# IRK.net
KiCad netlist of a schematic drawn in EAGLE
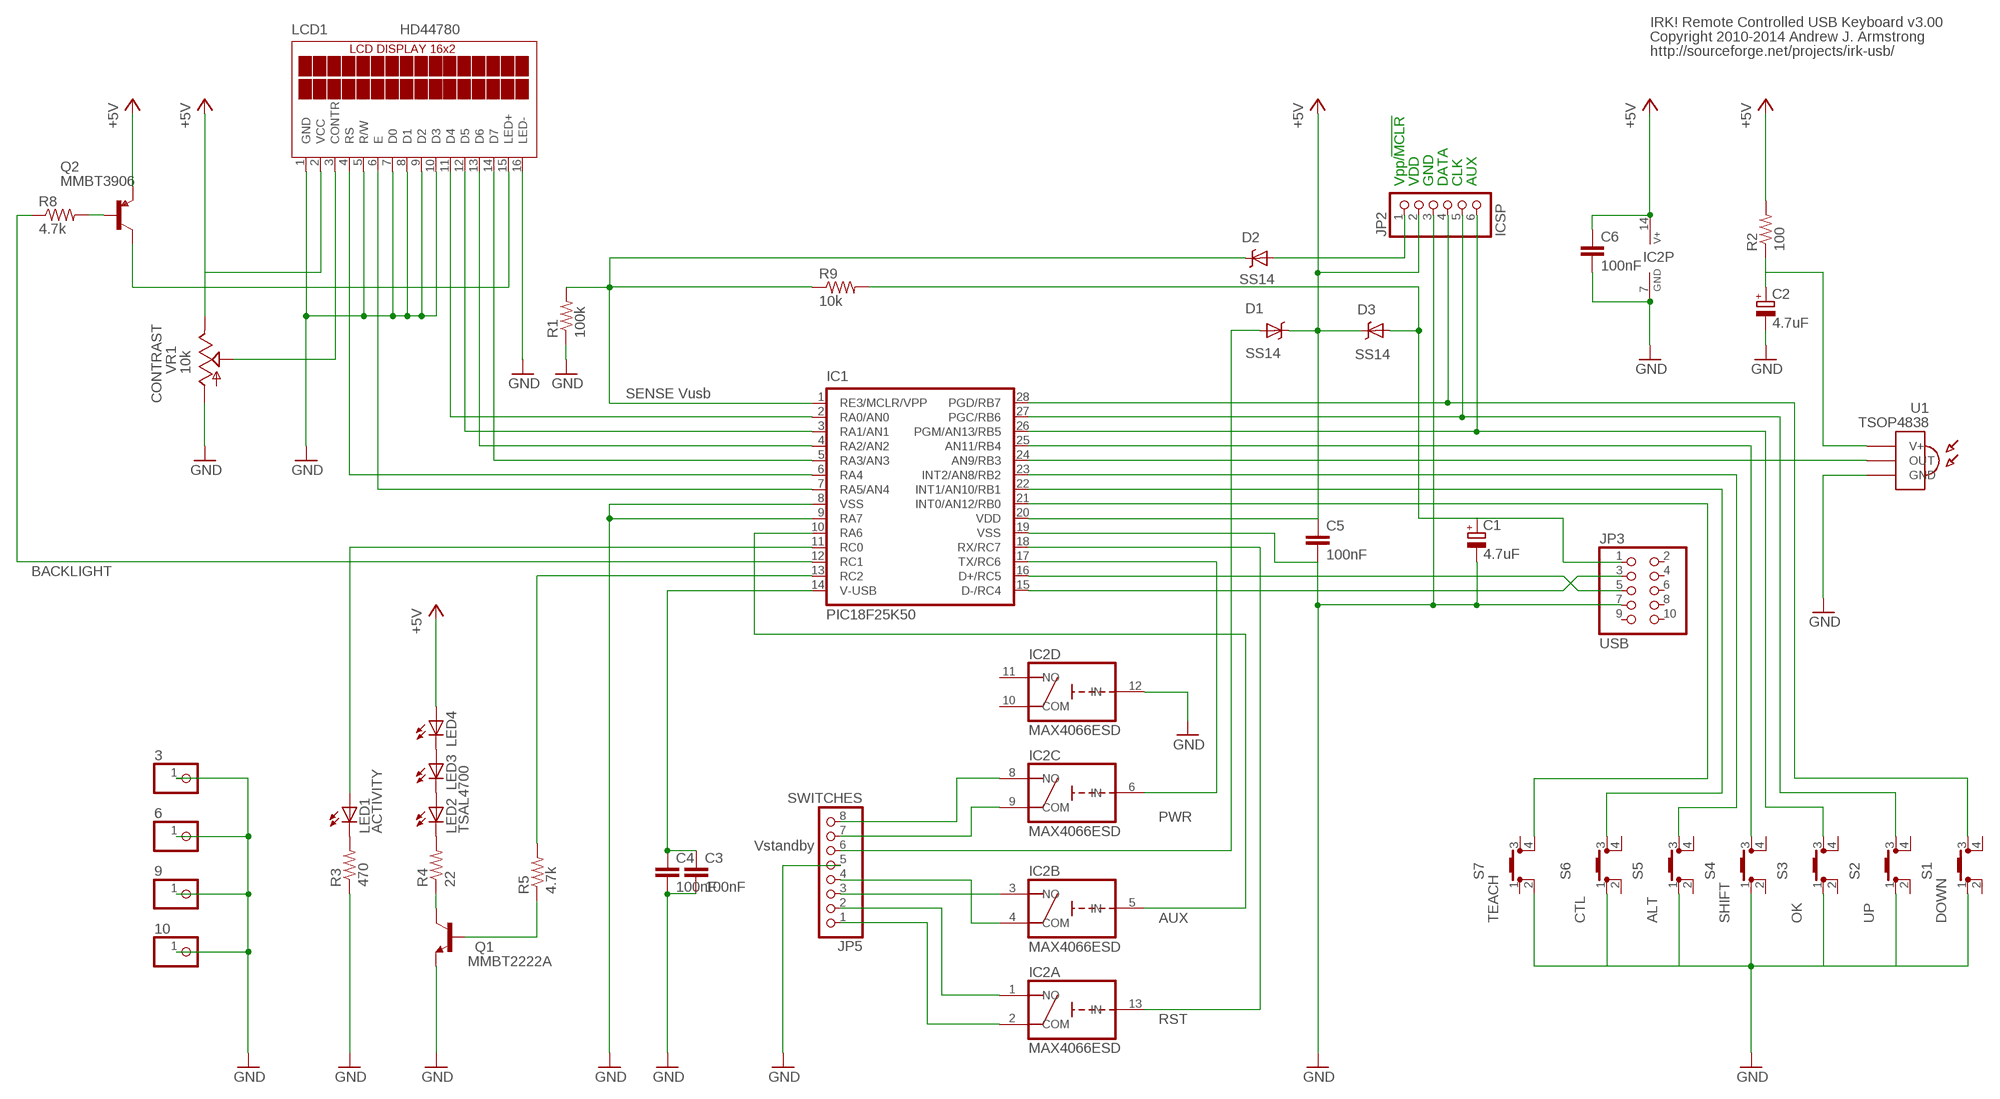
[diagram p0: schematic, sheet 1]

(export (version "E")
  (design (tool "Eeschema 10.0.6"))
  (components
    (comp (ref "3")
      (value "PINHD-1X1")
      (footprint "eagle-import:1X01")
      (libsource (lib "eagle-import") (part "PINHD-1X1"))
    )
    (comp (ref "6")
      (value "PINHD-1X1")
      (footprint "eagle-import:1X01")
      (libsource (lib "eagle-import") (part "PINHD-1X1"))
    )
    (comp (ref "9")
      (value "PINHD-1X1")
      (footprint "eagle-import:1X01")
      (libsource (lib "eagle-import") (part "PINHD-1X1"))
    )
    (comp (ref "10")
      (value "PINHD-1X1")
      (footprint "eagle-import:1X01")
      (libsource (lib "eagle-import") (part "PINHD-1X1"))
    )
    (comp (ref "C1")
      (value "4.7uF")
      (footprint "eagle-import:SMC_A")
      (libsource (lib "eagle-import") (part "CPOL-EUSMCA"))
    )
    (comp (ref "C2")
      (value "4.7uF")
      (footprint "eagle-import:SMC_A")
      (libsource (lib "eagle-import") (part "CPOL-EUSMCA"))
    )
    (comp (ref "C3")
      (value "100nF")
      (footprint "eagle-import:C0805")
      (libsource (lib "eagle-import") (part "C-EUC0805"))
    )
    (comp (ref "C4")
      (value "100nF")
      (footprint "eagle-import:C0805")
      (libsource (lib "eagle-import") (part "C-EUC0805"))
    )
    (comp (ref "C5")
      (value "100nF")
      (footprint "eagle-import:C0805")
      (libsource (lib "eagle-import") (part "C-EUC0805"))
    )
    (comp (ref "C6")
      (value "100nF")
      (footprint "eagle-import:C0805")
      (libsource (lib "eagle-import") (part "C-EUC0805"))
    )
    (comp (ref "D1")
      (value "SS14")
      (footprint "eagle-import:SMA-DIODE")
      (libsource (lib "eagle-import") (part "SS14"))
    )
    (comp (ref "D2")
      (value "SS14")
      (footprint "eagle-import:SMA-DIODE")
      (libsource (lib "eagle-import") (part "SS14"))
    )
    (comp (ref "D3")
      (value "SS14")
      (footprint "eagle-import:SMA-DIODE")
      (libsource (lib "eagle-import") (part "SS14"))
    )
    (comp (ref "IC1")
      (value "PIC18F25K50")
      (footprint "eagle-import:SO28W")
      (libsource (lib "eagle-import") (part "PIC18F25K50SO28W"))
    )
    (comp (ref "IC2")
      (value "MAX4066ESD")
      (footprint "eagle-import:SO14")
      (libsource (lib "eagle-import") (part "MAX4066ESD"))
    )
    (comp (ref "JP2")
      (value "ICSP")
      (footprint "eagle-import:1X06")
      (libsource (lib "eagle-import") (part "PINHD-1X6"))
    )
    (comp (ref "JP3")
      (value "USB")
      (footprint "eagle-import:2X05")
      (libsource (lib "eagle-import") (part "PINHD-2X5"))
    )
    (comp (ref "JP5")
      (value "SWITCHES")
      (footprint "eagle-import:1X08")
      (libsource (lib "eagle-import") (part "PINHD-1X8"))
    )
    (comp (ref "LCD1")
      (value "HD44780")
      (footprint "eagle-import:LCD_16X2")
      (libsource (lib "eagle-import") (part "HD44780"))
    )
    (comp (ref "LED1")
      (value "ACTIVITY")
      (footprint "eagle-import:LED5MM")
      (libsource (lib "eagle-import") (part "LED5MM"))
    )
    (comp (ref "LED2")
      (value "TSAL4700")
      (footprint "eagle-import:LED5MM")
      (libsource (lib "eagle-import") (part "LED5MM"))
    )
    (comp (ref "LED3")
      (value "LED5MM")
      (footprint "eagle-import:LED5MM")
      (libsource (lib "eagle-import") (part "LED5MM"))
    )
    (comp (ref "LED4")
      (value "LED5MM")
      (footprint "eagle-import:LED5MM")
      (libsource (lib "eagle-import") (part "LED5MM"))
    )
    (comp (ref "Q1")
      (value "MMBT2222A")
      (footprint "eagle-import:SOT23")
      (libsource (lib "eagle-import") (part "MMBT2222A"))
    )
    (comp (ref "Q2")
      (value "MMBT3906")
      (footprint "eagle-import:SOT23")
      (libsource (lib "eagle-import") (part "MMBT3906SOT23"))
    )
    (comp (ref "R1")
      (value "100k")
      (footprint "eagle-import:M1206")
      (libsource (lib "eagle-import") (part "R-US_M1206"))
    )
    (comp (ref "R2")
      (value "100")
      (footprint "eagle-import:M1206")
      (libsource (lib "eagle-import") (part "R-US_M1206"))
    )
    (comp (ref "R3")
      (value "470")
      (footprint "eagle-import:M1206")
      (libsource (lib "eagle-import") (part "R-US_M1206"))
    )
    (comp (ref "R4")
      (value "22")
      (footprint "eagle-import:M1206")
      (libsource (lib "eagle-import") (part "R-US_M1206"))
    )
    (comp (ref "R5")
      (value "4.7k")
      (footprint "eagle-import:M1206")
      (libsource (lib "eagle-import") (part "R-US_M1206"))
    )
    (comp (ref "R8")
      (value "4.7k")
      (footprint "eagle-import:M1206")
      (libsource (lib "eagle-import") (part "R-US_M1206"))
    )
    (comp (ref "R9")
      (value "10k")
      (footprint "eagle-import:M1206")
      (libsource (lib "eagle-import") (part "R-US_M1206"))
    )
    (comp (ref "S1")
      (value "DOWN")
      (footprint "eagle-import:PTH525-SM10")
      (libsource (lib "eagle-import") (part "C&K-PTS525-SM10"))
    )
    (comp (ref "S2")
      (value "UP")
      (footprint "eagle-import:PTH525-SM10")
      (libsource (lib "eagle-import") (part "C&K-PTS525-SM10"))
    )
    (comp (ref "S3")
      (value "OK")
      (footprint "eagle-import:PTH525-SM10")
      (libsource (lib "eagle-import") (part "C&K-PTS525-SM10"))
    )
    (comp (ref "S4")
      (value "SHIFT")
      (footprint "eagle-import:PTH525-SM10")
      (libsource (lib "eagle-import") (part "C&K-PTS525-SM10"))
    )
    (comp (ref "S5")
      (value "ALT")
      (footprint "eagle-import:PTH525-SM10")
      (libsource (lib "eagle-import") (part "C&K-PTS525-SM10"))
    )
    (comp (ref "S6")
      (value "CTL")
      (footprint "eagle-import:PTH525-SM10")
      (libsource (lib "eagle-import") (part "C&K-PTS525-SM10"))
    )
    (comp (ref "S7")
      (value "TEACH")
      (footprint "eagle-import:PTH525-SM10")
      (libsource (lib "eagle-import") (part "C&K-PTS525-SM10"))
    )
    (comp (ref "U1")
      (value "TSOP4838")
      (footprint "eagle-import:TSOP18XX")
      (libsource (lib "eagle-import") (part "TSOP4838"))
    )
    (comp (ref "VR1")
      (value "10k")
      (footprint "eagle-import:3303W")
      (libsource (lib "eagle-import") (part "TRIMPOT3303W"))
    )
  )
  (nets
    (net (code "1") (name "+5V") (class "Default")
      (node (ref "C5") (pin "1") (pinfunction "1_1") (pintype "passive"))
      (node (ref "C6") (pin "1") (pinfunction "1_1") (pintype "passive"))
      (node (ref "D1") (pin "K") (pinfunction "K_K") (pintype "passive"))
      (node (ref "D3") (pin "K") (pinfunction "K_K") (pintype "passive"))
      (node (ref "IC1") (pin "20") (pinfunction "VDD_20") (pintype "power_in"))
      (node (ref "IC2") (pin "14") (pinfunction "V+_14") (pintype "power_in"))
      (node (ref "JP2") (pin "2") (pinfunction "2_2") (pintype "passive"))
      (node (ref "LCD1") (pin "2") (pinfunction "VCC_2") (pintype "power_in"))
      (node (ref "LED4") (pin "A") (pinfunction "A_A") (pintype "passive"))
      (node (ref "Q2") (pin "2") (pinfunction "E_2") (pintype "passive"))
      (node (ref "R2") (pin "2") (pinfunction "2_2") (pintype "passive"))
      (node (ref "VR1") (pin "3") (pinfunction "E_3") (pintype "passive"))
    )
    (net (code "2") (name "GND") (class "Default")
      (node (ref "10") (pin "1") (pinfunction "1_1") (pintype "passive"))
      (node (ref "3") (pin "1") (pinfunction "1_1") (pintype "passive"))
      (node (ref "6") (pin "1") (pinfunction "1_1") (pintype "passive"))
      (node (ref "9") (pin "1") (pinfunction "1_1") (pintype "passive"))
      (node (ref "C1") (pin "-") (pinfunction "-_-") (pintype "passive"))
      (node (ref "C2") (pin "-") (pinfunction "-_-") (pintype "passive"))
      (node (ref "C3") (pin "2") (pinfunction "2_2") (pintype "passive"))
      (node (ref "C4") (pin "2") (pinfunction "2_2") (pintype "passive"))
      (node (ref "C5") (pin "2") (pinfunction "2_2") (pintype "passive"))
      (node (ref "C6") (pin "2") (pinfunction "2_2") (pintype "passive"))
      (node (ref "IC1") (pin "19") (pinfunction "VSS_19") (pintype "power_in"))
      (node (ref "IC1") (pin "8") (pinfunction "VSS_8") (pintype "power_in"))
      (node (ref "IC1") (pin "9") (pinfunction "RA7_9") (pintype "bidirectional"))
      (node (ref "IC2") (pin "12") (pinfunction "IN_12") (pintype "input"))
      (node (ref "IC2") (pin "7") (pinfunction "GND_7") (pintype "power_in"))
      (node (ref "JP2") (pin "3") (pinfunction "3_3") (pintype "passive"))
      (node (ref "JP3") (pin "7") (pinfunction "7_7") (pintype "passive"))
      (node (ref "JP5") (pin "5") (pinfunction "5_5") (pintype "passive"))
      (node (ref "LCD1") (pin "1") (pinfunction "GND_1") (pintype "power_in"))
      (node (ref "LCD1") (pin "10") (pinfunction "D3_10") (pintype "input"))
      (node (ref "LCD1") (pin "16") (pinfunction "LED-_16") (pintype "passive"))
      (node (ref "LCD1") (pin "5") (pinfunction "R/W_5") (pintype "input"))
      (node (ref "LCD1") (pin "7") (pinfunction "D0_7") (pintype "input"))
      (node (ref "LCD1") (pin "8") (pinfunction "D1_8") (pintype "input"))
      (node (ref "LCD1") (pin "9") (pinfunction "D2_9") (pintype "input"))
      (node (ref "Q1") (pin "2") (pinfunction "E_2") (pintype "passive"))
      (node (ref "R1") (pin "1") (pinfunction "1_1") (pintype "passive"))
      (node (ref "R3") (pin "1") (pinfunction "1_1") (pintype "passive"))
      (node (ref "S1") (pin "1") (pinfunction "1_1") (pintype "passive"))
      (node (ref "S2") (pin "1") (pinfunction "1_1") (pintype "passive"))
      (node (ref "S3") (pin "1") (pinfunction "1_1") (pintype "passive"))
      (node (ref "S4") (pin "1") (pinfunction "1_1") (pintype "passive"))
      (node (ref "S5") (pin "1") (pinfunction "1_1") (pintype "passive"))
      (node (ref "S6") (pin "1") (pinfunction "1_1") (pintype "passive"))
      (node (ref "S7") (pin "2") (pinfunction "2_2") (pintype "passive"))
      (node (ref "U1") (pin "GND") (pinfunction "GND_GND") (pintype "power_in"))
      (node (ref "VR1") (pin "1") (pinfunction "A_1") (pintype "passive"))
    )
    (net (code "3") (name "Net-(C1-Pad+)") (class "Default")
      (node (ref "C1") (pin "+") (pinfunction "+_+") (pintype "passive"))
      (node (ref "D3") (pin "A") (pinfunction "A_A") (pintype "passive"))
      (node (ref "JP3") (pin "1") (pinfunction "1_1") (pintype "passive"))
      (node (ref "R9") (pin "2") (pinfunction "2_2") (pintype "passive"))
    )
    (net (code "4") (name "Net-(D1-PadA)") (class "Default")
      (node (ref "D1") (pin "A") (pinfunction "A_A") (pintype "passive"))
      (node (ref "JP5") (pin "6") (pinfunction "6_6") (pintype "passive"))
    )
    (net (code "5") (name "Net-(D2-PadA)") (class "Default")
      (node (ref "D2") (pin "A") (pinfunction "A_A") (pintype "passive"))
      (node (ref "JP2") (pin "1") (pinfunction "1_1") (pintype "passive"))
    )
    (net (code "6") (name "Net-(IC1-AN9{slash}RB3)") (class "Default")
      (node (ref "IC1") (pin "24") (pinfunction "AN9/RB3_24") (pintype "bidirectional"))
      (node (ref "U1") (pin "OUT") (pinfunction "OUT_OUT") (pintype "open_collector"))
    )
    (net (code "7") (name "Net-(IC1-AN11{slash}RB4)") (class "Default")
      (node (ref "IC1") (pin "25") (pinfunction "AN11/RB4_25") (pintype "bidirectional"))
      (node (ref "S4") (pin "3") (pinfunction "3_3") (pintype "passive"))
    )
    (net (code "8") (name "Net-(IC1-D+{slash}RC5)") (class "Default")
      (node (ref "IC1") (pin "16") (pinfunction "D+/RC5_16") (pintype "bidirectional"))
      (node (ref "JP3") (pin "5") (pinfunction "5_5") (pintype "passive"))
    )
    (net (code "9") (name "Net-(IC1-D-{slash}RC4)") (class "Default")
      (node (ref "IC1") (pin "15") (pinfunction "D-/RC4_15") (pintype "bidirectional"))
      (node (ref "JP3") (pin "3") (pinfunction "3_3") (pintype "passive"))
    )
    (net (code "10") (name "Net-(IC1-INT0{slash}AN12{slash}RB0)") (class "Default")
      (node (ref "IC1") (pin "21") (pinfunction "INT0/AN12/RB0_21") (pintype "bidirectional"))
      (node (ref "S7") (pin "4") (pinfunction "4_4") (pintype "passive"))
    )
    (net (code "11") (name "Net-(IC1-INT1{slash}AN10{slash}RB1)") (class "Default")
      (node (ref "IC1") (pin "22") (pinfunction "INT1/AN10/RB1_22") (pintype "bidirectional"))
      (node (ref "S6") (pin "3") (pinfunction "3_3") (pintype "passive"))
    )
    (net (code "12") (name "Net-(IC1-INT2{slash}AN8{slash}RB2)") (class "Default")
      (node (ref "IC1") (pin "23") (pinfunction "INT2/AN8/RB2_23") (pintype "bidirectional"))
      (node (ref "S5") (pin "3") (pinfunction "3_3") (pintype "passive"))
    )
    (net (code "13") (name "Net-(IC1-PGC{slash}RB6)") (class "Default")
      (node (ref "IC1") (pin "27") (pinfunction "PGC/RB6_27") (pintype "bidirectional"))
      (node (ref "JP2") (pin "5") (pinfunction "5_5") (pintype "passive"))
      (node (ref "S2") (pin "3") (pinfunction "3_3") (pintype "passive"))
    )
    (net (code "14") (name "Net-(IC1-PGD{slash}RB7)") (class "Default")
      (node (ref "IC1") (pin "28") (pinfunction "PGD/RB7_28") (pintype "bidirectional"))
      (node (ref "JP2") (pin "4") (pinfunction "4_4") (pintype "passive"))
      (node (ref "S1") (pin "3") (pinfunction "3_3") (pintype "passive"))
    )
    (net (code "15") (name "Net-(IC1-PGM{slash}AN13{slash}RB5)") (class "Default")
      (node (ref "IC1") (pin "26") (pinfunction "PGM/AN13/RB5_26") (pintype "bidirectional"))
      (node (ref "JP2") (pin "6") (pinfunction "6_6") (pintype "passive"))
      (node (ref "S3") (pin "3") (pinfunction "3_3") (pintype "passive"))
    )
    (net (code "16") (name "Net-(IC1-RA0{slash}AN0)") (class "Default")
      (node (ref "IC1") (pin "2") (pinfunction "RA0/AN0_2") (pintype "bidirectional"))
      (node (ref "LCD1") (pin "11") (pinfunction "D4_11") (pintype "input"))
    )
    (net (code "17") (name "Net-(IC1-RA1{slash}AN1)") (class "Default")
      (node (ref "IC1") (pin "3") (pinfunction "RA1/AN1_3") (pintype "bidirectional"))
      (node (ref "LCD1") (pin "12") (pinfunction "D5_12") (pintype "input"))
    )
    (net (code "18") (name "Net-(IC1-RA2{slash}AN2)") (class "Default")
      (node (ref "IC1") (pin "4") (pinfunction "RA2/AN2_4") (pintype "bidirectional"))
      (node (ref "LCD1") (pin "13") (pinfunction "D6_13") (pintype "input"))
    )
    (net (code "19") (name "Net-(IC1-RA3{slash}AN3)") (class "Default")
      (node (ref "IC1") (pin "5") (pinfunction "RA3/AN3_5") (pintype "bidirectional"))
      (node (ref "LCD1") (pin "14") (pinfunction "D7_14") (pintype "input"))
    )
    (net (code "20") (name "Net-(IC1-RA4)") (class "Default")
      (node (ref "IC1") (pin "6") (pinfunction "RA4_6") (pintype "bidirectional"))
      (node (ref "LCD1") (pin "4") (pinfunction "RS_4") (pintype "input"))
    )
    (net (code "21") (name "Net-(IC1-RA5{slash}AN4)") (class "Default")
      (node (ref "IC1") (pin "7") (pinfunction "RA5/AN4_7") (pintype "bidirectional"))
      (node (ref "LCD1") (pin "6") (pinfunction "E_6") (pintype "input"))
    )
    (net (code "22") (name "Net-(IC1-RA6)") (class "Default")
      (node (ref "IC1") (pin "10") (pinfunction "RA6_10") (pintype "bidirectional"))
      (node (ref "IC2") (pin "5") (pinfunction "IN_5") (pintype "input"))
    )
    (net (code "23") (name "Net-(IC1-RC0)") (class "Default")
      (node (ref "IC1") (pin "11") (pinfunction "RC0_11") (pintype "bidirectional"))
      (node (ref "LED1") (pin "A") (pinfunction "A_A") (pintype "passive"))
    )
    (net (code "24") (name "Net-(IC1-RC1)") (class "Default")
      (node (ref "IC1") (pin "12") (pinfunction "RC1_12") (pintype "bidirectional"))
      (node (ref "R8") (pin "1") (pinfunction "1_1") (pintype "passive"))
    )
    (net (code "25") (name "Net-(IC1-RC2)") (class "Default")
      (node (ref "IC1") (pin "13") (pinfunction "RC2_13") (pintype "bidirectional"))
      (node (ref "R5") (pin "2") (pinfunction "2_2") (pintype "passive"))
    )
    (net (code "26") (name "Net-(IC1-RE3{slash}MCLR{slash}VPP)") (class "Default")
      (node (ref "D2") (pin "K") (pinfunction "K_K") (pintype "passive"))
      (node (ref "IC1") (pin "1") (pinfunction "RE3/MCLR/VPP_1") (pintype "bidirectional"))
      (node (ref "R1") (pin "2") (pinfunction "2_2") (pintype "passive"))
      (node (ref "R9") (pin "1") (pinfunction "1_1") (pintype "passive"))
    )
    (net (code "27") (name "Net-(IC1-RX{slash}RC7)") (class "Default")
      (node (ref "IC1") (pin "18") (pinfunction "RX/RC7_18") (pintype "bidirectional"))
      (node (ref "IC2") (pin "13") (pinfunction "IN_13") (pintype "input"))
    )
    (net (code "28") (name "Net-(IC1-TX{slash}RC6)") (class "Default")
      (node (ref "IC1") (pin "17") (pinfunction "TX/RC6_17") (pintype "bidirectional"))
      (node (ref "IC2") (pin "6") (pinfunction "IN_6") (pintype "input"))
    )
    (net (code "29") (name "Net-(IC1-V-USB)") (class "Default")
      (node (ref "C3") (pin "1") (pinfunction "1_1") (pintype "passive"))
      (node (ref "C4") (pin "1") (pinfunction "1_1") (pintype "passive"))
      (node (ref "IC1") (pin "14") (pinfunction "V-USB_14") (pintype "bidirectional"))
    )
    (net (code "30") (name "Net-(IC2A-COM)") (class "Default")
      (node (ref "IC2") (pin "2") (pinfunction "COM_2") (pintype "tri_state"))
      (node (ref "JP5") (pin "1") (pinfunction "1_1") (pintype "passive"))
    )
    (net (code "31") (name "Net-(IC2A-NO)") (class "Default")
      (node (ref "IC2") (pin "1") (pinfunction "NO_1") (pintype "tri_state"))
      (node (ref "JP5") (pin "2") (pinfunction "2_2") (pintype "passive"))
    )
    (net (code "32") (name "Net-(IC2B-COM)") (class "Default")
      (node (ref "IC2") (pin "4") (pinfunction "COM_4") (pintype "tri_state"))
      (node (ref "JP5") (pin "4") (pinfunction "4_4") (pintype "passive"))
    )
    (net (code "33") (name "Net-(IC2B-NO)") (class "Default")
      (node (ref "IC2") (pin "3") (pinfunction "NO_3") (pintype "tri_state"))
      (node (ref "JP5") (pin "3") (pinfunction "3_3") (pintype "passive"))
    )
    (net (code "34") (name "Net-(IC2C-COM)") (class "Default")
      (node (ref "IC2") (pin "9") (pinfunction "COM_9") (pintype "tri_state"))
      (node (ref "JP5") (pin "7") (pinfunction "7_7") (pintype "passive"))
    )
    (net (code "35") (name "Net-(IC2C-NO)") (class "Default")
      (node (ref "IC2") (pin "8") (pinfunction "NO_8") (pintype "tri_state"))
      (node (ref "JP5") (pin "8") (pinfunction "8_8") (pintype "passive"))
    )
    (net (code "36") (name "Net-(LCD1-CONTR)") (class "Default")
      (node (ref "LCD1") (pin "3") (pinfunction "CONTR_3") (pintype "input"))
      (node (ref "VR1") (pin "2") (pinfunction "S_2") (pintype "passive"))
    )
    (net (code "37") (name "Net-(LCD1-LED+)") (class "Default")
      (node (ref "LCD1") (pin "15") (pinfunction "LED+_15") (pintype "passive"))
      (node (ref "Q2") (pin "3") (pinfunction "C_3") (pintype "passive"))
    )
    (net (code "38") (name "Net-(LED1-C)") (class "Default")
      (node (ref "LED1") (pin "K") (pinfunction "C_K") (pintype "passive"))
      (node (ref "R3") (pin "2") (pinfunction "2_2") (pintype "passive"))
    )
    (net (code "39") (name "Net-(LED2-C)") (class "Default")
      (node (ref "LED2") (pin "K") (pinfunction "C_K") (pintype "passive"))
      (node (ref "R4") (pin "2") (pinfunction "2_2") (pintype "passive"))
    )
    (net (code "40") (name "Net-(LED3-C)") (class "Default")
      (node (ref "LED2") (pin "A") (pinfunction "A_A") (pintype "passive"))
      (node (ref "LED3") (pin "K") (pinfunction "C_K") (pintype "passive"))
    )
    (net (code "41") (name "Net-(LED4-C)") (class "Default")
      (node (ref "LED3") (pin "A") (pinfunction "A_A") (pintype "passive"))
      (node (ref "LED4") (pin "K") (pinfunction "C_K") (pintype "passive"))
    )
    (net (code "42") (name "Net-(Q1-B)") (class "Default")
      (node (ref "Q1") (pin "1") (pinfunction "B_1") (pintype "passive"))
      (node (ref "R5") (pin "1") (pinfunction "1_1") (pintype "passive"))
    )
    (net (code "43") (name "Net-(Q1-C)") (class "Default")
      (node (ref "Q1") (pin "3") (pinfunction "C_3") (pintype "passive"))
      (node (ref "R4") (pin "1") (pinfunction "1_1") (pintype "passive"))
    )
    (net (code "44") (name "Net-(Q2-B)") (class "Default")
      (node (ref "Q2") (pin "1") (pinfunction "B_1") (pintype "passive"))
      (node (ref "R8") (pin "2") (pinfunction "2_2") (pintype "passive"))
    )
    (net (code "45") (name "Net-(U1-V+)") (class "Default")
      (node (ref "C2") (pin "+") (pinfunction "+_+") (pintype "passive"))
      (node (ref "R2") (pin "1") (pinfunction "1_1") (pintype "passive"))
      (node (ref "U1") (pin "VCC") (pinfunction "V+_VCC") (pintype "power_in"))
    )
    (net (code "46") (name "unconnected-(IC2D-COM-Pad10)") (class "Default")
      (node (ref "IC2") (pin "10") (pinfunction "COM_10") (pintype "tri_state"))
    )
    (net (code "47") (name "unconnected-(IC2D-NO-Pad11)") (class "Default")
      (node (ref "IC2") (pin "11") (pinfunction "NO_11") (pintype "tri_state"))
    )
    (net (code "48") (name "unconnected-(JP3-Pad2)") (class "Default")
      (node (ref "JP3") (pin "2") (pinfunction "2_2") (pintype "passive"))
    )
    (net (code "49") (name "unconnected-(JP3-Pad4)") (class "Default")
      (node (ref "JP3") (pin "4") (pinfunction "4_4") (pintype "passive"))
    )
    (net (code "50") (name "unconnected-(JP3-Pad6)") (class "Default")
      (node (ref "JP3") (pin "6") (pinfunction "6_6") (pintype "passive"))
    )
    (net (code "51") (name "unconnected-(JP3-Pad8)") (class "Default")
      (node (ref "JP3") (pin "8") (pinfunction "8_8") (pintype "passive"))
    )
    (net (code "52") (name "unconnected-(JP3-Pad9)") (class "Default")
      (node (ref "JP3") (pin "9") (pinfunction "9_9") (pintype "passive"))
    )
    (net (code "53") (name "unconnected-(JP3-Pad10)") (class "Default")
      (node (ref "JP3") (pin "10") (pinfunction "10_10") (pintype "passive"))
    )
    (net (code "54") (name "unconnected-(S1-Pad2)") (class "Default")
      (node (ref "S1") (pin "2") (pinfunction "2_2") (pintype "passive"))
    )
    (net (code "55") (name "unconnected-(S1-Pad4)") (class "Default")
      (node (ref "S1") (pin "4") (pinfunction "4_4") (pintype "passive"))
    )
    (net (code "56") (name "unconnected-(S2-Pad2)") (class "Default")
      (node (ref "S2") (pin "2") (pinfunction "2_2") (pintype "passive"))
    )
    (net (code "57") (name "unconnected-(S2-Pad4)") (class "Default")
      (node (ref "S2") (pin "4") (pinfunction "4_4") (pintype "passive"))
    )
    (net (code "58") (name "unconnected-(S3-Pad2)") (class "Default")
      (node (ref "S3") (pin "2") (pinfunction "2_2") (pintype "passive"))
    )
    (net (code "59") (name "unconnected-(S3-Pad4)") (class "Default")
      (node (ref "S3") (pin "4") (pinfunction "4_4") (pintype "passive"))
    )
    (net (code "60") (name "unconnected-(S4-Pad2)") (class "Default")
      (node (ref "S4") (pin "2") (pinfunction "2_2") (pintype "passive"))
    )
    (net (code "61") (name "unconnected-(S4-Pad4)") (class "Default")
      (node (ref "S4") (pin "4") (pinfunction "4_4") (pintype "passive"))
    )
    (net (code "62") (name "unconnected-(S5-Pad2)") (class "Default")
      (node (ref "S5") (pin "2") (pinfunction "2_2") (pintype "passive"))
    )
    (net (code "63") (name "unconnected-(S5-Pad4)") (class "Default")
      (node (ref "S5") (pin "4") (pinfunction "4_4") (pintype "passive"))
    )
    (net (code "64") (name "unconnected-(S6-Pad2)") (class "Default")
      (node (ref "S6") (pin "2") (pinfunction "2_2") (pintype "passive"))
    )
    (net (code "65") (name "unconnected-(S6-Pad4)") (class "Default")
      (node (ref "S6") (pin "4") (pinfunction "4_4") (pintype "passive"))
    )
    (net (code "66") (name "unconnected-(S7-Pad1)") (class "Default")
      (node (ref "S7") (pin "1") (pinfunction "1_1") (pintype "passive"))
    )
    (net (code "67") (name "unconnected-(S7-Pad3)") (class "Default")
      (node (ref "S7") (pin "3") (pinfunction "3_3") (pintype "passive"))
    )
  )
)
